# czujnik.net
KiCad netlist of a schematic drawn in EAGLE
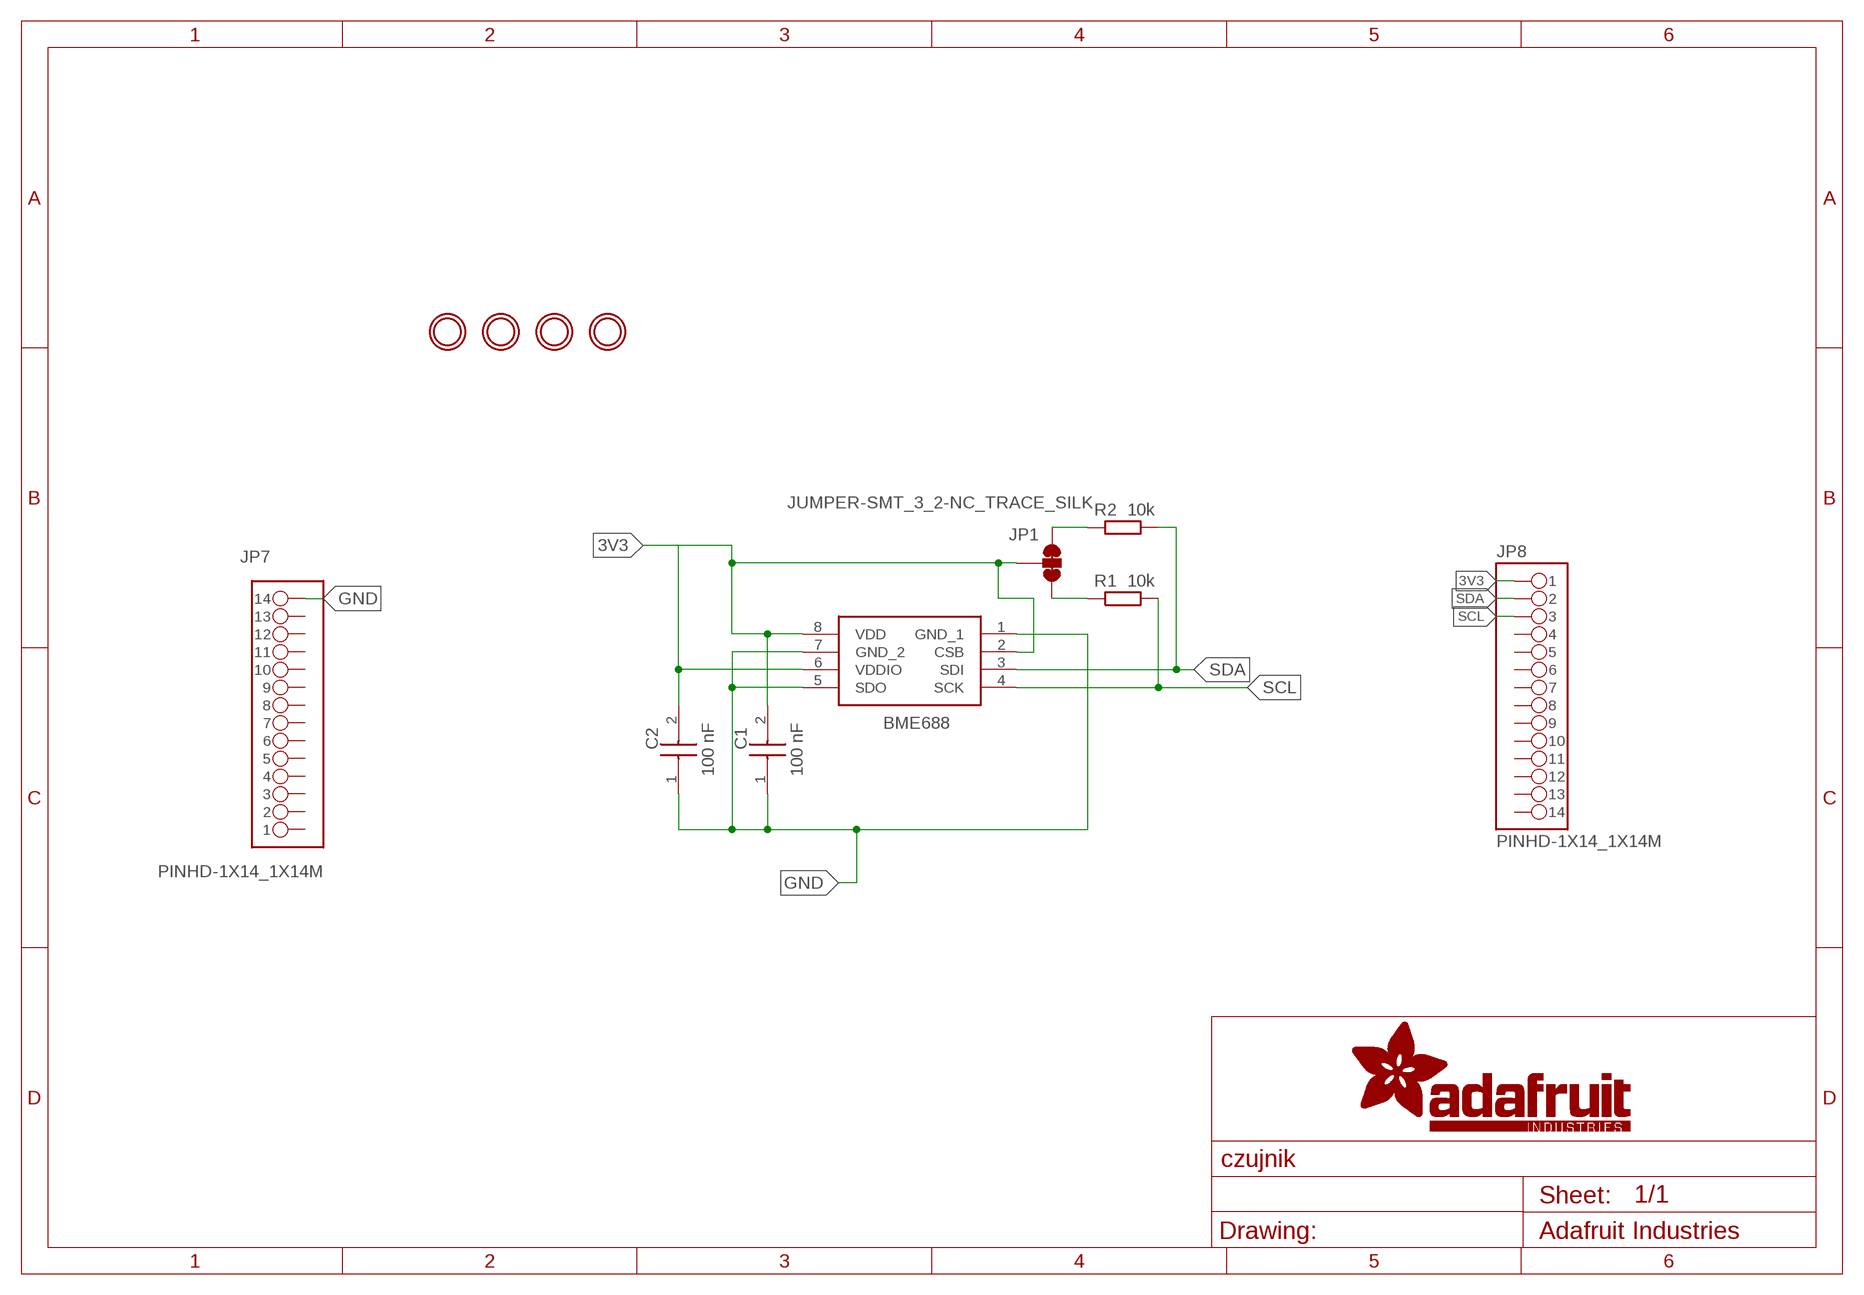
[diagram p0: schematic, sheet 1]

(export (version "E")
  (design (tool "Eeschema 10.0.6"))
  (components
    (comp (ref "BME688")
      (value "BME688")
      (footprint "eagle-import:BME688")
      (fields (field (name "MOUSER_PART_NUMBER") "262-BME688"))
      (libsource (lib "eagle-import") (part "BME688"))
    )
    (comp (ref "C1")
      (value "C0603X104K1RACTU")
      (footprint "eagle-import:CAPC1608X100N")
      (description "100 nF")
      (fields (field (name "MOUSER_PART_NUMBER") "80-C0603X104K1RACTU"))
      (libsource (lib "eagle-import") (part "C0603X104K1RACTU"))
    )
    (comp (ref "C2")
      (value "C0603X104K1RACTU")
      (footprint "eagle-import:CAPC1608X100N")
      (description "100 nF")
      (fields (field (name "MOUSER_PART_NUMBER") "80-C0603X104K1RACTU"))
      (libsource (lib "eagle-import") (part "C0603X104K1RACTU"))
    )
    (comp (ref "JP1")
      (value "JUMPER-SMT_3_2-NC_TRACE_SILK")
      (footprint "eagle-import:SMT-JUMPER_3_2-NC_TRACE_SILK")
      (libsource (lib "eagle-import") (part "JUMPER-SMT_3_2-NC_TRACE_SILK"))
    )
    (comp (ref "JP7")
      (value "PINHD-1X14_1X14M")
      (footprint "eagle-import:1X14")
      (libsource (lib "eagle-import") (part "PINHD-1X14_1X14M"))
    )
    (comp (ref "JP8")
      (value "PINHD-1X14_1X14M")
      (footprint "eagle-import:1X14")
      (libsource (lib "eagle-import") (part "PINHD-1X14_1X14M"))
    )
    (comp (ref "R1")
      (value "10k")
      (footprint "eagle-import:RESC1005X40")
      (libsource (lib "eagle-import") (part "RESISTOR_CHIP-0402(1005-METRIC)_"))
    )
    (comp (ref "R2")
      (value "10k")
      (footprint "eagle-import:RESC1005X40")
      (libsource (lib "eagle-import") (part "RESISTOR_CHIP-0402(1005-METRIC)_"))
    )
    (comp (ref "U$2")
      (value "MOUNTINGHOLE2.5")
      (footprint "eagle-import:MOUNTINGHOLE_2.5_PLATED")
      (libsource (lib "eagle-import") (part "MOUNTINGHOLE2.5"))
    )
    (comp (ref "U$3")
      (value "MOUNTINGHOLE2.5")
      (footprint "eagle-import:MOUNTINGHOLE_2.5_PLATED")
      (libsource (lib "eagle-import") (part "MOUNTINGHOLE2.5"))
    )
    (comp (ref "U$4")
      (value "MOUNTINGHOLE2.5")
      (footprint "eagle-import:MOUNTINGHOLE_2.5_PLATED")
      (libsource (lib "eagle-import") (part "MOUNTINGHOLE2.5"))
    )
    (comp (ref "U$6")
      (value "MOUNTINGHOLE2.5")
      (footprint "eagle-import:MOUNTINGHOLE_2.5_PLATED")
      (libsource (lib "eagle-import") (part "MOUNTINGHOLE2.5"))
    )
  )
  (nets
    (net (code "1") (name "3V3") (class "Default")
      (node (ref "BME688") (pin "2") (pinfunction "CSB_2") (pintype "bidirectional"))
      (node (ref "BME688") (pin "6") (pinfunction "VDDIO_6") (pintype "bidirectional"))
      (node (ref "BME688") (pin "8") (pinfunction "VDD_8") (pintype "bidirectional"))
      (node (ref "C1") (pin "2") (pinfunction "2_2") (pintype "bidirectional"))
      (node (ref "C2") (pin "2") (pinfunction "2_2") (pintype "bidirectional"))
      (node (ref "JP1") (pin "2") (pinfunction "2_2") (pintype "passive"))
      (node (ref "JP8") (pin "1") (pinfunction "1_1") (pintype "bidirectional"))
    )
    (net (code "2") (name "GND") (class "Default")
      (node (ref "BME688") (pin "1") (pinfunction "GND_1_1") (pintype "bidirectional"))
      (node (ref "BME688") (pin "5") (pinfunction "SDO_5") (pintype "bidirectional"))
      (node (ref "BME688") (pin "7") (pinfunction "GND_2_7") (pintype "bidirectional"))
      (node (ref "C1") (pin "1") (pinfunction "1_1") (pintype "bidirectional"))
      (node (ref "C2") (pin "1") (pinfunction "1_1") (pintype "bidirectional"))
      (node (ref "JP7") (pin "14") (pinfunction "14_14") (pintype "bidirectional"))
    )
    (net (code "3") (name "Net-(JP1-Pad1)") (class "Default")
      (node (ref "JP1") (pin "1") (pinfunction "1_1") (pintype "passive"))
      (node (ref "R2") (pin "1") (pinfunction "1_1") (pintype "passive"))
    )
    (net (code "4") (name "Net-(JP1-Pad3)") (class "Default")
      (node (ref "JP1") (pin "3") (pinfunction "3_3") (pintype "passive"))
      (node (ref "R1") (pin "1") (pinfunction "1_1") (pintype "passive"))
    )
    (net (code "5") (name "SCL") (class "Default")
      (node (ref "BME688") (pin "4") (pinfunction "SCK_4") (pintype "bidirectional"))
      (node (ref "JP8") (pin "3") (pinfunction "3_3") (pintype "bidirectional"))
      (node (ref "R1") (pin "2") (pinfunction "2_2") (pintype "passive"))
    )
    (net (code "6") (name "SDA") (class "Default")
      (node (ref "BME688") (pin "3") (pinfunction "SDI_3") (pintype "bidirectional"))
      (node (ref "JP8") (pin "2") (pinfunction "2_2") (pintype "bidirectional"))
      (node (ref "R2") (pin "2") (pinfunction "2_2") (pintype "passive"))
    )
    (net (code "7") (name "unconnected-(JP7-Pad1)") (class "Default")
      (node (ref "JP7") (pin "1") (pinfunction "1_1") (pintype "bidirectional"))
    )
    (net (code "8") (name "unconnected-(JP7-Pad2)") (class "Default")
      (node (ref "JP7") (pin "2") (pinfunction "2_2") (pintype "bidirectional"))
    )
    (net (code "9") (name "unconnected-(JP7-Pad3)") (class "Default")
      (node (ref "JP7") (pin "3") (pinfunction "3_3") (pintype "bidirectional"))
    )
    (net (code "10") (name "unconnected-(JP7-Pad4)") (class "Default")
      (node (ref "JP7") (pin "4") (pinfunction "4_4") (pintype "bidirectional"))
    )
    (net (code "11") (name "unconnected-(JP7-Pad5)") (class "Default")
      (node (ref "JP7") (pin "5") (pinfunction "5_5") (pintype "bidirectional"))
    )
    (net (code "12") (name "unconnected-(JP7-Pad6)") (class "Default")
      (node (ref "JP7") (pin "6") (pinfunction "6_6") (pintype "bidirectional"))
    )
    (net (code "13") (name "unconnected-(JP7-Pad7)") (class "Default")
      (node (ref "JP7") (pin "7") (pinfunction "7_7") (pintype "bidirectional"))
    )
    (net (code "14") (name "unconnected-(JP7-Pad8)") (class "Default")
      (node (ref "JP7") (pin "8") (pinfunction "8_8") (pintype "bidirectional"))
    )
    (net (code "15") (name "unconnected-(JP7-Pad9)") (class "Default")
      (node (ref "JP7") (pin "9") (pinfunction "9_9") (pintype "bidirectional"))
    )
    (net (code "16") (name "unconnected-(JP7-Pad10)") (class "Default")
      (node (ref "JP7") (pin "10") (pinfunction "10_10") (pintype "bidirectional"))
    )
    (net (code "17") (name "unconnected-(JP7-Pad11)") (class "Default")
      (node (ref "JP7") (pin "11") (pinfunction "11_11") (pintype "bidirectional"))
    )
    (net (code "18") (name "unconnected-(JP7-Pad12)") (class "Default")
      (node (ref "JP7") (pin "12") (pinfunction "12_12") (pintype "bidirectional"))
    )
    (net (code "19") (name "unconnected-(JP7-Pad13)") (class "Default")
      (node (ref "JP7") (pin "13") (pinfunction "13_13") (pintype "bidirectional"))
    )
    (net (code "20") (name "unconnected-(JP8-Pad4)") (class "Default")
      (node (ref "JP8") (pin "4") (pinfunction "4_4") (pintype "bidirectional"))
    )
    (net (code "21") (name "unconnected-(JP8-Pad5)") (class "Default")
      (node (ref "JP8") (pin "5") (pinfunction "5_5") (pintype "bidirectional"))
    )
    (net (code "22") (name "unconnected-(JP8-Pad6)") (class "Default")
      (node (ref "JP8") (pin "6") (pinfunction "6_6") (pintype "bidirectional"))
    )
    (net (code "23") (name "unconnected-(JP8-Pad7)") (class "Default")
      (node (ref "JP8") (pin "7") (pinfunction "7_7") (pintype "bidirectional"))
    )
    (net (code "24") (name "unconnected-(JP8-Pad8)") (class "Default")
      (node (ref "JP8") (pin "8") (pinfunction "8_8") (pintype "bidirectional"))
    )
    (net (code "25") (name "unconnected-(JP8-Pad9)") (class "Default")
      (node (ref "JP8") (pin "9") (pinfunction "9_9") (pintype "bidirectional"))
    )
    (net (code "26") (name "unconnected-(JP8-Pad10)") (class "Default")
      (node (ref "JP8") (pin "10") (pinfunction "10_10") (pintype "bidirectional"))
    )
    (net (code "27") (name "unconnected-(JP8-Pad11)") (class "Default")
      (node (ref "JP8") (pin "11") (pinfunction "11_11") (pintype "bidirectional"))
    )
    (net (code "28") (name "unconnected-(JP8-Pad12)") (class "Default")
      (node (ref "JP8") (pin "12") (pinfunction "12_12") (pintype "bidirectional"))
    )
    (net (code "29") (name "unconnected-(JP8-Pad13)") (class "Default")
      (node (ref "JP8") (pin "13") (pinfunction "13_13") (pintype "bidirectional"))
    )
    (net (code "30") (name "unconnected-(JP8-Pad14)") (class "Default")
      (node (ref "JP8") (pin "14") (pinfunction "14_14") (pintype "bidirectional"))
    )
  )
)
